# Main.net
KiCad netlist of a schematic drawn in Altium Designer
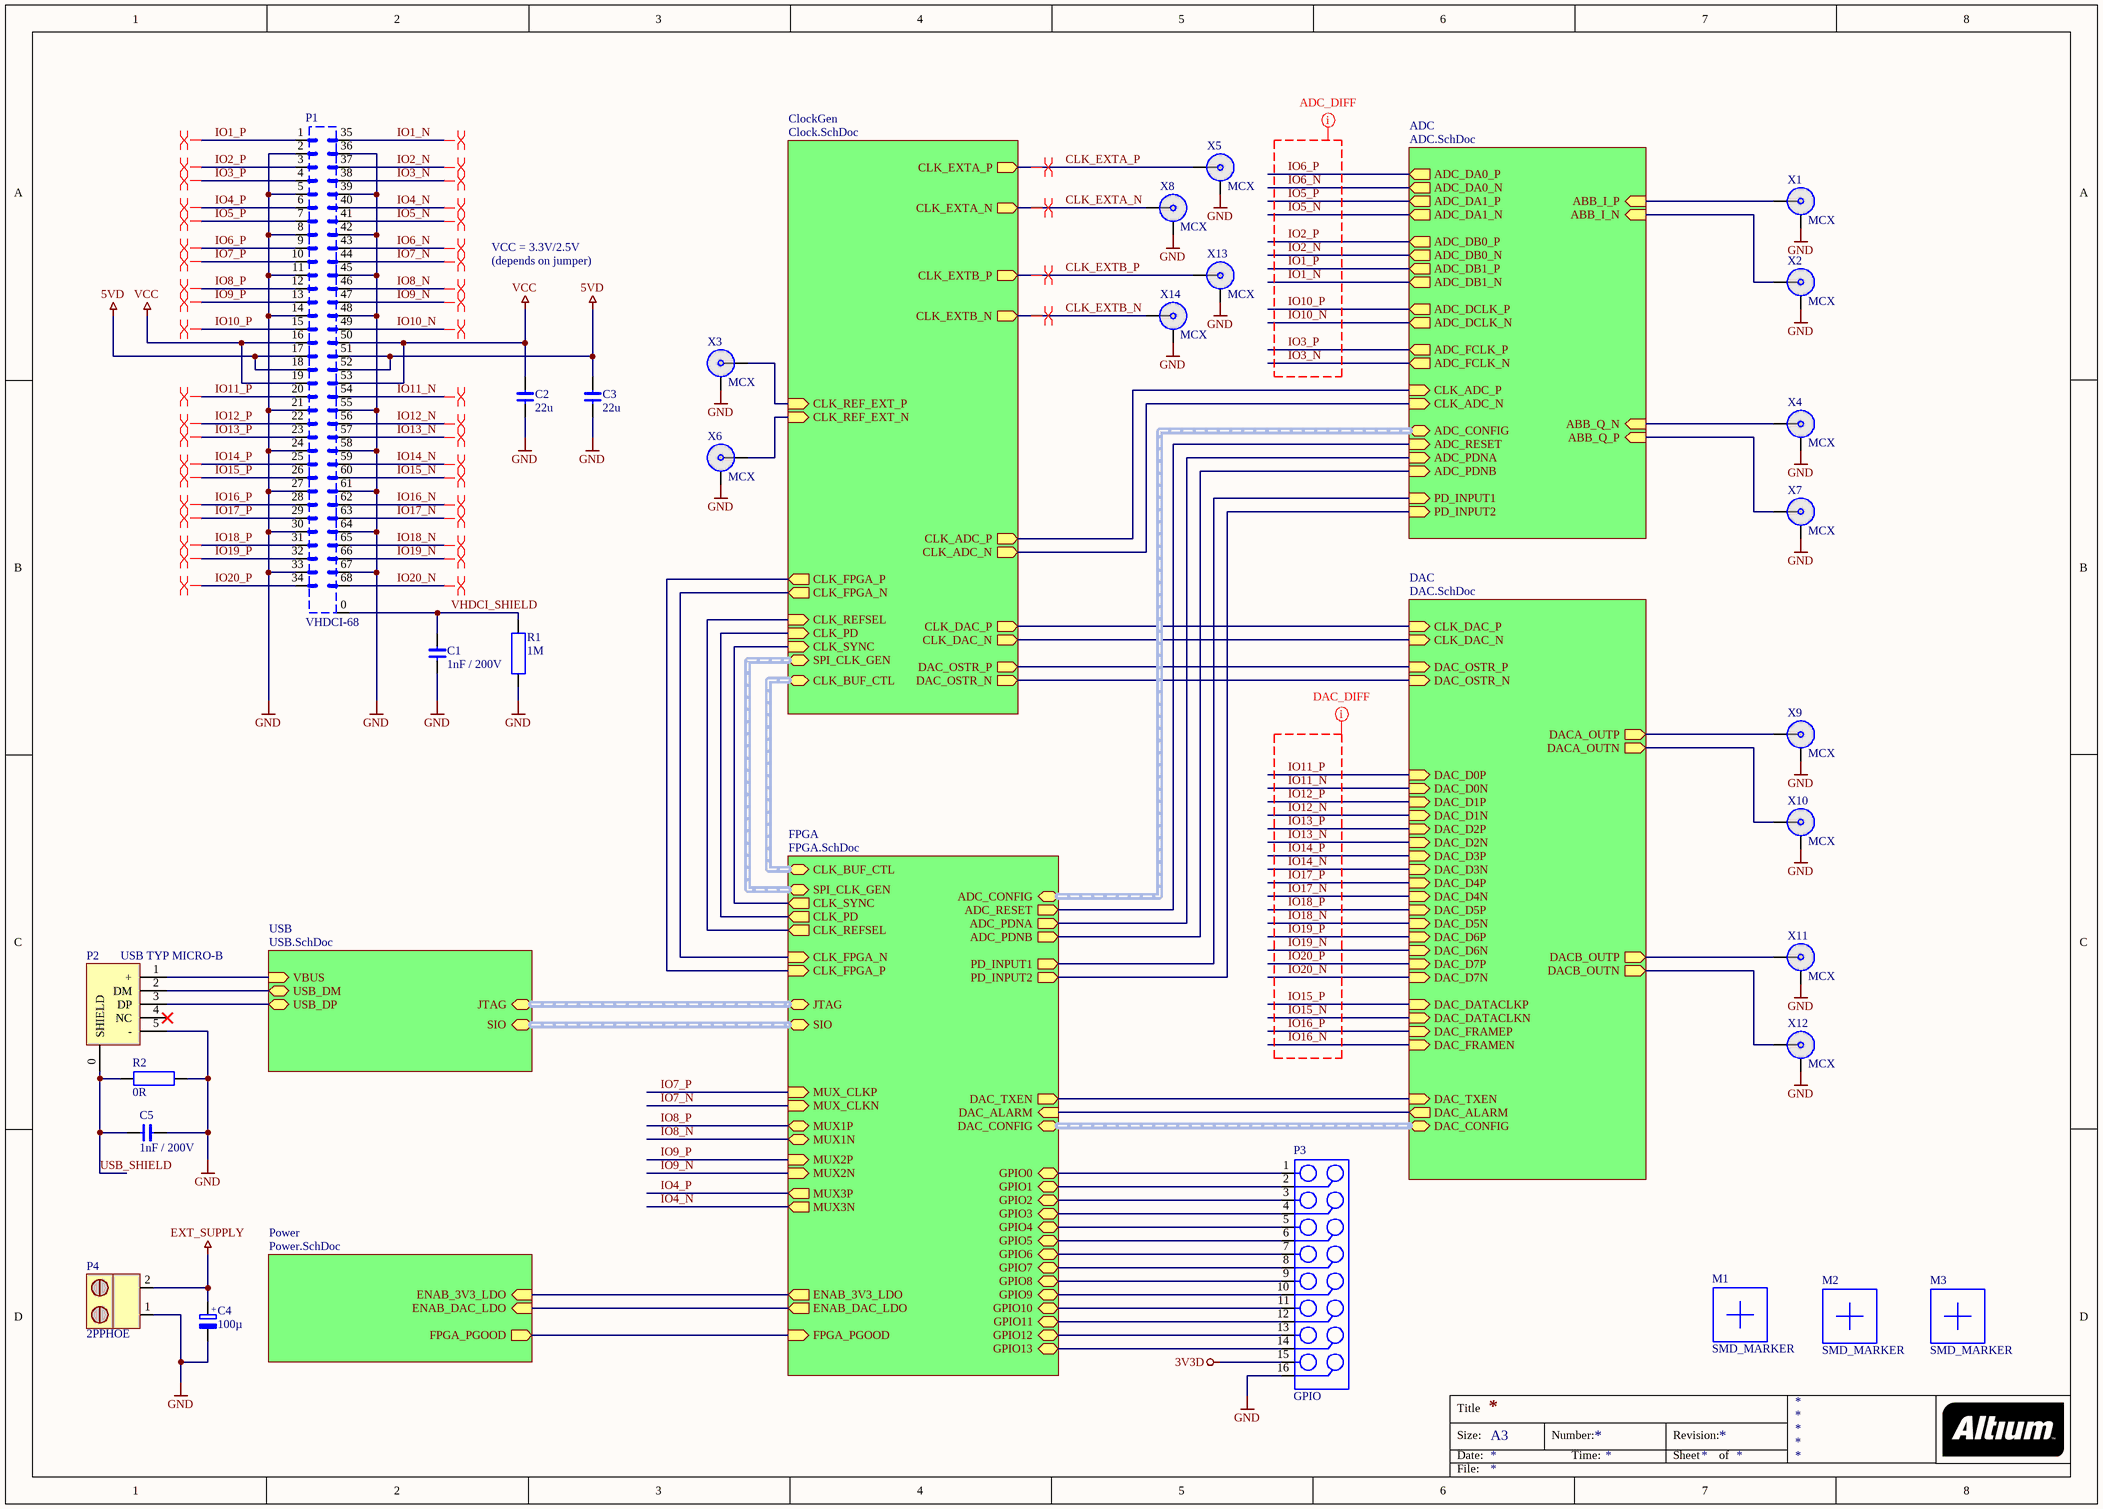
[diagram p0: Main.SchDoc]

(export (version "E")
  (design (tool "Eeschema 10.0.6"))
  (components
    (comp (ref "C1")
      (value "1nF / 200V")
      (footprint "1206")
      (description "C")
      (libsource (lib "RCL") (part "C"))
    )
    (comp (ref "C2") (value "22u") (footprint "1206") (description "C") (libsource (lib "RCL") (part "C")))
    (comp (ref "C3") (value "22u") (footprint "1206") (description "C") (libsource (lib "RCL") (part "C")))
    (comp (ref "C4")
      (value "100µ")
      (footprint "SMD_ELKO_6.3")
      (description "EEH-ZA1E101XP")
      (libsource (lib "RCL") (part "ELCO"))
    )
    (comp (ref "C5")
      (value "1nF / 200V")
      (footprint "1206")
      (description "C")
      (libsource (lib "RCL") (part "C"))
    )
    (comp (ref "M1")
      (value "SMD_MARKER")
      (footprint "SMDMark100 - nopaste")
      (description "SMD MARKER")
      (libsource (lib "SPECIAL1") (part "SMD_MARKER"))
    )
    (comp (ref "M2")
      (value "SMD_MARKER")
      (footprint "SMDMark100 - nopaste")
      (description "SMD MARKER")
      (libsource (lib "SPECIAL1") (part "SMD_MARKER"))
    )
    (comp (ref "M3")
      (value "SMD_MARKER")
      (footprint "SMDMark100 - nopaste")
      (description "SMD MARKER")
      (libsource (lib "SPECIAL1") (part "SMD_MARKER"))
    )
    (comp (ref "P1")
      (value "VHDCI-68")
      (footprint "VHDCI-68_M")
      (description "68-Pin VHDCI Connector")
      (libsource (lib "Private") (part "MALE_VHDCI-68"))
    )
    (comp (ref "P2")
      (value "USB TYP MICRO-B")
      (footprint "USB_MICRO_B_SMD_4DIP")
      (description "10118194-0001LF")
      (libsource (lib "CONNECT1") (part "USB TYP MICRO-B"))
    )
    (comp (ref "P3")
      (value "GPIO")
      (footprint "16POL_PF2")
      (description "16POLPF")
      (libsource (lib "CONNECT1") (part "16POLPF"))
    )
    (comp (ref "P4")
      (value "2PPHOE")
      (footprint "2PPHOE")
      (description "Steckbare Scharubklemme 2pol.")
      (libsource (lib "CONNECT1") (part "2PPHOE"))
    )
    (comp (ref "R1") (value "1M") (footprint "1206") (description "R") (libsource (lib "RCL") (part "R")))
    (comp (ref "R2") (value "0R") (footprint "1206") (description "R") (libsource (lib "RCL") (part "R")))
    (comp (ref "X1")
      (value "MCX")
      (footprint "MCX_TH")
      (description "MCX Connector")
      (libsource (lib "Private") (part "MCX"))
    )
    (comp (ref "X2")
      (value "MCX")
      (footprint "MCX_TH")
      (description "MCX Connector")
      (libsource (lib "Private") (part "MCX"))
    )
    (comp (ref "X3")
      (value "MCX")
      (footprint "MCX_TH")
      (description "MCX Connector")
      (libsource (lib "Private") (part "MCX"))
    )
    (comp (ref "X4")
      (value "MCX")
      (footprint "MCX_TH")
      (description "MCX Connector")
      (libsource (lib "Private") (part "MCX"))
    )
    (comp (ref "X5")
      (value "MCX")
      (footprint "MCX_TH")
      (description "MCX Connector")
      (libsource (lib "Private") (part "MCX"))
    )
    (comp (ref "X6")
      (value "MCX")
      (footprint "MCX_TH")
      (description "MCX Connector")
      (libsource (lib "Private") (part "MCX"))
    )
    (comp (ref "X7")
      (value "MCX")
      (footprint "MCX_TH")
      (description "MCX Connector")
      (libsource (lib "Private") (part "MCX"))
    )
    (comp (ref "X8")
      (value "MCX")
      (footprint "MCX_TH")
      (description "MCX Connector")
      (libsource (lib "Private") (part "MCX"))
    )
    (comp (ref "X9")
      (value "MCX")
      (footprint "MCX_TH")
      (description "MCX Connector")
      (libsource (lib "Private") (part "MCX"))
    )
    (comp (ref "X10")
      (value "MCX")
      (footprint "MCX_TH")
      (description "MCX Connector")
      (libsource (lib "Private") (part "MCX"))
    )
    (comp (ref "X11")
      (value "MCX")
      (footprint "MCX_TH")
      (description "MCX Connector")
      (libsource (lib "Private") (part "MCX"))
    )
    (comp (ref "X12")
      (value "MCX")
      (footprint "MCX_TH")
      (description "MCX Connector")
      (libsource (lib "Private") (part "MCX"))
    )
    (comp (ref "X13")
      (value "MCX")
      (footprint "MCX_TH")
      (description "MCX Connector")
      (libsource (lib "Private") (part "MCX"))
    )
    (comp (ref "X14")
      (value "MCX")
      (footprint "MCX_TH")
      (description "MCX Connector")
      (libsource (lib "Private") (part "MCX"))
    )
  )
  (nets
    (net (code "1") (name "/ABB_I_N") (class "Default") (node (ref "X2") (pin "2") (pintype "passive")))
    (net (code "2") (name "/ABB_I_P") (class "Default") (node (ref "X1") (pin "2") (pintype "passive")))
    (net (code "3") (name "/ABB_Q_N") (class "Default") (node (ref "X4") (pin "2") (pintype "passive")))
    (net (code "4") (name "/ABB_Q_P") (class "Default") (node (ref "X7") (pin "2") (pintype "passive")))
    (net (code "14") (name "/CLK_EXTA_N") (class "Default") (node (ref "X8") (pin "2") (pintype "passive")))
    (net (code "15") (name "/CLK_EXTA_P") (class "Default") (node (ref "X5") (pin "2") (pintype "passive")))
    (net (code "16") (name "/CLK_EXTB_N") (class "Default") (node (ref "X14") (pin "2") (pintype "passive")))
    (net (code "17") (name "/CLK_EXTB_P") (class "Default") (node (ref "X13") (pin "2") (pintype "passive")))
    (net (code "22") (name "/CLK_REF_EXT_N") (class "Default")
      (node (ref "X6") (pin "2") (pintype "passive"))
    )
    (net (code "23") (name "/CLK_REF_EXT_P") (class "Default")
      (node (ref "X3") (pin "2") (pintype "passive"))
    )
    (net (code "25") (name "/DACA_OUTN") (class "Default") (node (ref "X10") (pin "2") (pintype "passive")))
    (net (code "26") (name "/DACA_OUTP") (class "Default") (node (ref "X9") (pin "2") (pintype "passive")))
    (net (code "27") (name "/DACB_OUTN") (class "Default") (node (ref "X12") (pin "2") (pintype "passive")))
    (net (code "28") (name "/DACB_OUTP") (class "Default") (node (ref "X11") (pin "2") (pintype "passive")))
    (net (code "37") (name "/GPIO0") (class "Default")
      (node (ref "P3") (pin "1") (pinfunction "1_1") (pintype "passive"))
    )
    (net (code "38") (name "/GPIO1") (class "Default")
      (node (ref "P3") (pin "2") (pinfunction "2_2") (pintype "passive"))
    )
    (net (code "39") (name "/GPIO2") (class "Default")
      (node (ref "P3") (pin "3") (pinfunction "3_3") (pintype "passive"))
    )
    (net (code "40") (name "/GPIO3") (class "Default")
      (node (ref "P3") (pin "4") (pinfunction "4_4") (pintype "passive"))
    )
    (net (code "41") (name "/GPIO4") (class "Default")
      (node (ref "P3") (pin "5") (pinfunction "5_5") (pintype "passive"))
    )
    (net (code "42") (name "/GPIO5") (class "Default")
      (node (ref "P3") (pin "6") (pinfunction "6_6") (pintype "passive"))
    )
    (net (code "43") (name "/GPIO6") (class "Default")
      (node (ref "P3") (pin "7") (pinfunction "7_7") (pintype "passive"))
    )
    (net (code "44") (name "/GPIO7") (class "Default")
      (node (ref "P3") (pin "8") (pinfunction "8_8") (pintype "passive"))
    )
    (net (code "45") (name "/GPIO8") (class "Default")
      (node (ref "P3") (pin "9") (pinfunction "9_9") (pintype "passive"))
    )
    (net (code "46") (name "/GPIO9") (class "Default")
      (node (ref "P3") (pin "10") (pinfunction "10_10") (pintype "passive"))
    )
    (net (code "47") (name "/GPIO10") (class "Default")
      (node (ref "P3") (pin "11") (pinfunction "11_11") (pintype "passive"))
    )
    (net (code "48") (name "/GPIO11") (class "Default")
      (node (ref "P3") (pin "12") (pinfunction "12_12") (pintype "passive"))
    )
    (net (code "49") (name "/GPIO12") (class "Default")
      (node (ref "P3") (pin "13") (pinfunction "13_13") (pintype "passive"))
    )
    (net (code "50") (name "/GPIO13") (class "Default")
      (node (ref "P3") (pin "14") (pinfunction "14_14") (pintype "passive"))
    )
    (net (code "51") (name "/IO1_N") (class "Default")
      (node (ref "P1") (pin "35") (pinfunction "35_35") (pintype "passive"))
    )
    (net (code "52") (name "/IO1_P") (class "Default")
      (node (ref "P1") (pin "1") (pinfunction "1_1") (pintype "passive"))
    )
    (net (code "53") (name "/IO2_N") (class "Default")
      (node (ref "P1") (pin "37") (pinfunction "37_37") (pintype "passive"))
    )
    (net (code "54") (name "/IO2_P") (class "Default")
      (node (ref "P1") (pin "3") (pinfunction "3_3") (pintype "passive"))
    )
    (net (code "55") (name "/IO3_N") (class "Default")
      (node (ref "P1") (pin "38") (pinfunction "38_38") (pintype "passive"))
    )
    (net (code "56") (name "/IO3_P") (class "Default")
      (node (ref "P1") (pin "4") (pinfunction "4_4") (pintype "passive"))
    )
    (net (code "57") (name "/IO4_N") (class "Default")
      (node (ref "P1") (pin "40") (pinfunction "40_40") (pintype "passive"))
    )
    (net (code "58") (name "/IO4_P") (class "Default")
      (node (ref "P1") (pin "6") (pinfunction "6_6") (pintype "passive"))
    )
    (net (code "59") (name "/IO5_N") (class "Default")
      (node (ref "P1") (pin "41") (pinfunction "41_41") (pintype "passive"))
    )
    (net (code "60") (name "/IO5_P") (class "Default")
      (node (ref "P1") (pin "7") (pinfunction "7_7") (pintype "passive"))
    )
    (net (code "61") (name "/IO6_N") (class "Default")
      (node (ref "P1") (pin "43") (pinfunction "43_43") (pintype "passive"))
    )
    (net (code "62") (name "/IO6_P") (class "Default")
      (node (ref "P1") (pin "9") (pinfunction "9_9") (pintype "passive"))
    )
    (net (code "63") (name "/IO7_N") (class "Default")
      (node (ref "P1") (pin "44") (pinfunction "44_44") (pintype "passive"))
    )
    (net (code "64") (name "/IO7_P") (class "Default")
      (node (ref "P1") (pin "10") (pinfunction "10_10") (pintype "passive"))
    )
    (net (code "65") (name "/IO8_N") (class "Default")
      (node (ref "P1") (pin "46") (pinfunction "46_46") (pintype "passive"))
    )
    (net (code "66") (name "/IO8_P") (class "Default")
      (node (ref "P1") (pin "12") (pinfunction "12_12") (pintype "passive"))
    )
    (net (code "67") (name "/IO9_N") (class "Default")
      (node (ref "P1") (pin "47") (pinfunction "47_47") (pintype "passive"))
    )
    (net (code "68") (name "/IO9_P") (class "Default")
      (node (ref "P1") (pin "13") (pinfunction "13_13") (pintype "passive"))
    )
    (net (code "69") (name "/IO10_N") (class "Default")
      (node (ref "P1") (pin "49") (pinfunction "49_49") (pintype "passive"))
    )
    (net (code "70") (name "/IO10_P") (class "Default")
      (node (ref "P1") (pin "15") (pinfunction "15_15") (pintype "passive"))
    )
    (net (code "71") (name "/IO11_N") (class "Default")
      (node (ref "P1") (pin "54") (pinfunction "54_54") (pintype "passive"))
    )
    (net (code "72") (name "/IO11_P") (class "Default")
      (node (ref "P1") (pin "20") (pinfunction "20_20") (pintype "passive"))
    )
    (net (code "73") (name "/IO12_N") (class "Default")
      (node (ref "P1") (pin "56") (pinfunction "56_56") (pintype "passive"))
    )
    (net (code "74") (name "/IO12_P") (class "Default")
      (node (ref "P1") (pin "22") (pinfunction "22_22") (pintype "passive"))
    )
    (net (code "75") (name "/IO13_N") (class "Default")
      (node (ref "P1") (pin "57") (pinfunction "57_57") (pintype "passive"))
    )
    (net (code "76") (name "/IO13_P") (class "Default")
      (node (ref "P1") (pin "23") (pinfunction "23_23") (pintype "passive"))
    )
    (net (code "77") (name "/IO14_N") (class "Default")
      (node (ref "P1") (pin "59") (pinfunction "59_59") (pintype "passive"))
    )
    (net (code "78") (name "/IO14_P") (class "Default")
      (node (ref "P1") (pin "25") (pinfunction "25_25") (pintype "passive"))
    )
    (net (code "79") (name "/IO15_N") (class "Default")
      (node (ref "P1") (pin "60") (pinfunction "60_60") (pintype "passive"))
    )
    (net (code "80") (name "/IO15_P") (class "Default")
      (node (ref "P1") (pin "26") (pinfunction "26_26") (pintype "passive"))
    )
    (net (code "81") (name "/IO16_N") (class "Default")
      (node (ref "P1") (pin "62") (pinfunction "62_62") (pintype "passive"))
    )
    (net (code "82") (name "/IO16_P") (class "Default")
      (node (ref "P1") (pin "28") (pinfunction "28_28") (pintype "passive"))
    )
    (net (code "83") (name "/IO17_N") (class "Default")
      (node (ref "P1") (pin "63") (pinfunction "63_63") (pintype "passive"))
    )
    (net (code "84") (name "/IO17_P") (class "Default")
      (node (ref "P1") (pin "29") (pinfunction "29_29") (pintype "passive"))
    )
    (net (code "85") (name "/IO18_N") (class "Default")
      (node (ref "P1") (pin "65") (pinfunction "65_65") (pintype "passive"))
    )
    (net (code "86") (name "/IO18_P") (class "Default")
      (node (ref "P1") (pin "31") (pinfunction "31_31") (pintype "passive"))
    )
    (net (code "87") (name "/IO19_N") (class "Default")
      (node (ref "P1") (pin "66") (pinfunction "66_66") (pintype "passive"))
    )
    (net (code "88") (name "/IO19_P") (class "Default")
      (node (ref "P1") (pin "32") (pinfunction "32_32") (pintype "passive"))
    )
    (net (code "89") (name "/IO20_N") (class "Default")
      (node (ref "P1") (pin "68") (pinfunction "68_68") (pintype "passive"))
    )
    (net (code "90") (name "/IO20_P") (class "Default")
      (node (ref "P1") (pin "34") (pinfunction "34_34") (pintype "passive"))
    )
    (net (code "96") (name "/USB_DM") (class "Default")
      (node (ref "P2") (pin "2") (pinfunction "DM_2") (pintype "passive"))
    )
    (net (code "97") (name "/USB_DP") (class "Default")
      (node (ref "P2") (pin "3") (pinfunction "DP_3") (pintype "passive"))
    )
    (net (code "98") (name "/USB_SHIELD") (class "Default")
      (node (ref "C5") (pin "2") (pinfunction "2_2") (pintype "passive"))
      (node (ref "P2") (pin "0") (pinfunction "SHIELD_0") (pintype "passive"))
      (node (ref "R2") (pin "2") (pinfunction "2_2") (pintype "passive"))
    )
    (net (code "99") (name "/VBUS") (class "Default")
      (node (ref "P2") (pin "1") (pinfunction "+_1") (pintype "passive"))
    )
    (net (code "100") (name "/VHDCI_SHIELD") (class "Default")
      (node (ref "C1") (pin "1") (pinfunction "1_1") (pintype "passive"))
      (node (ref "P1") (pin "0") (pinfunction "SHIELD_0") (pintype "passive"))
      (node (ref "R1") (pin "1") (pinfunction "1_1") (pintype "passive"))
    )
    (net (code "101") (name "3V3D") (class "Default")
      (node (ref "P3") (pin "15") (pinfunction "15_15") (pintype "passive"))
    )
    (net (code "102") (name "5VD") (class "Default")
      (node (ref "C3") (pin "1") (pinfunction "1_1") (pintype "passive"))
      (node (ref "P1") (pin "17") (pinfunction "17_17") (pintype "passive"))
      (node (ref "P1") (pin "18") (pinfunction "18_18") (pintype "passive"))
      (node (ref "P1") (pin "51") (pinfunction "51_51") (pintype "passive"))
      (node (ref "P1") (pin "52") (pinfunction "52_52") (pintype "passive"))
    )
    (net (code "103") (name "EXT_SUPPLY") (class "Default")
      (node (ref "C4") (pin "1") (pinfunction "+_1") (pintype "passive"))
      (node (ref "P4") (pin "2") (pinfunction "2_2") (pintype "passive"))
    )
    (net (code "104") (name "GND") (class "Default")
      (node (ref "C1") (pin "2") (pinfunction "2_2") (pintype "passive"))
      (node (ref "C2") (pin "2") (pinfunction "2_2") (pintype "passive"))
      (node (ref "C3") (pin "2") (pinfunction "2_2") (pintype "passive"))
      (node (ref "C4") (pin "2") (pinfunction "-_2") (pintype "passive"))
      (node (ref "C5") (pin "1") (pinfunction "1_1") (pintype "passive"))
      (node (ref "P1") (pin "11") (pinfunction "11_11") (pintype "passive"))
      (node (ref "P1") (pin "14") (pinfunction "14_14") (pintype "passive"))
      (node (ref "P1") (pin "2") (pinfunction "2_2") (pintype "passive"))
      (node (ref "P1") (pin "21") (pinfunction "21_21") (pintype "passive"))
      (node (ref "P1") (pin "24") (pinfunction "24_24") (pintype "passive"))
      (node (ref "P1") (pin "27") (pinfunction "27_27") (pintype "passive"))
      (node (ref "P1") (pin "30") (pinfunction "30_30") (pintype "passive"))
      (node (ref "P1") (pin "33") (pinfunction "33_33") (pintype "passive"))
      (node (ref "P1") (pin "36") (pinfunction "36_36") (pintype "passive"))
      (node (ref "P1") (pin "39") (pinfunction "39_39") (pintype "passive"))
      (node (ref "P1") (pin "42") (pinfunction "42_42") (pintype "passive"))
      (node (ref "P1") (pin "45") (pinfunction "45_45") (pintype "passive"))
      (node (ref "P1") (pin "48") (pinfunction "48_48") (pintype "passive"))
      (node (ref "P1") (pin "5") (pinfunction "5_5") (pintype "passive"))
      (node (ref "P1") (pin "55") (pinfunction "55_55") (pintype "passive"))
      (node (ref "P1") (pin "58") (pinfunction "58_58") (pintype "passive"))
      (node (ref "P1") (pin "61") (pinfunction "61_61") (pintype "passive"))
      (node (ref "P1") (pin "64") (pinfunction "64_64") (pintype "passive"))
      (node (ref "P1") (pin "67") (pinfunction "67_67") (pintype "passive"))
      (node (ref "P1") (pin "8") (pinfunction "8_8") (pintype "passive"))
      (node (ref "P2") (pin "5") (pinfunction "-_5") (pintype "passive"))
      (node (ref "P3") (pin "16") (pinfunction "16_16") (pintype "passive"))
      (node (ref "P4") (pin "1") (pinfunction "1_1") (pintype "passive"))
      (node (ref "R1") (pin "2") (pinfunction "2_2") (pintype "passive"))
      (node (ref "R2") (pin "1") (pinfunction "1_1") (pintype "passive"))
      (node (ref "X1") (pin "1") (pintype "passive"))
      (node (ref "X10") (pin "1") (pintype "passive"))
      (node (ref "X11") (pin "1") (pintype "passive"))
      (node (ref "X12") (pin "1") (pintype "passive"))
      (node (ref "X13") (pin "1") (pintype "passive"))
      (node (ref "X14") (pin "1") (pintype "passive"))
      (node (ref "X2") (pin "1") (pintype "passive"))
      (node (ref "X3") (pin "1") (pintype "passive"))
      (node (ref "X4") (pin "1") (pintype "passive"))
      (node (ref "X5") (pin "1") (pintype "passive"))
      (node (ref "X6") (pin "1") (pintype "passive"))
      (node (ref "X7") (pin "1") (pintype "passive"))
      (node (ref "X8") (pin "1") (pintype "passive"))
      (node (ref "X9") (pin "1") (pintype "passive"))
    )
    (net (code "105") (name "VCC") (class "Default")
      (node (ref "C2") (pin "1") (pinfunction "1_1") (pintype "passive"))
      (node (ref "P1") (pin "16") (pinfunction "16_16") (pintype "passive"))
      (node (ref "P1") (pin "19") (pinfunction "19_19") (pintype "passive"))
      (node (ref "P1") (pin "50") (pinfunction "50_50") (pintype "passive"))
      (node (ref "P1") (pin "53") (pinfunction "53_53") (pintype "passive"))
    )
    (net (code "106") (name "unconnected-(P2-NC-Pad4)") (class "Default")
      (node (ref "P2") (pin "4") (pinfunction "NC_4") (pintype "passive+no_connect"))
    )
  )
)
